# PSU.net
KiCad netlist of a schematic drawn in Altium Designer
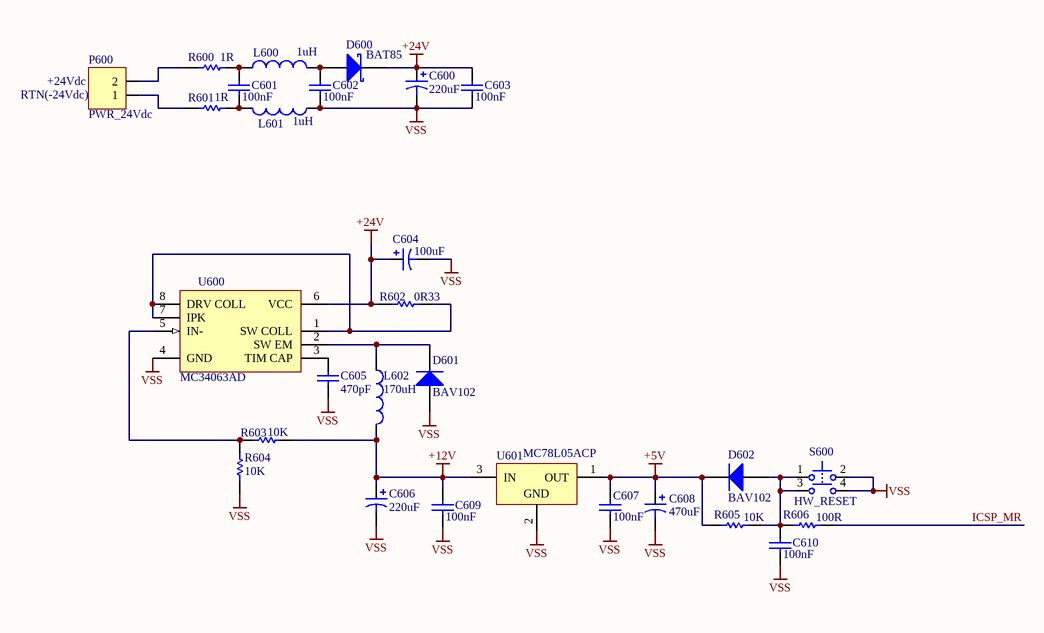
[diagram p0: PSU.SchDoc]

(export (version "E")
  (design (tool "Eeschema 10.0.6"))
  (components
    (comp (ref "C600")
      (value "220uF")
      (footprint "E")
      (description "Solid Aluminum Capacitor with Organic Semiconductor Electrolyte: 100uF, 10V, Bulk Pack")
      (fields (field (name "PUBLISHER") "Altium Limited"))
      (libsource (lib "Vishay Electrolytic Radial-Lead Capacitor") (part "94SA107X0010EBP"))
    )
    (comp (ref "C601")
      (value "100nF")
      (footprint "1206")
      (description "Ceramic Chip Capacitor - Standard")
      (fields (field (name "PUBLISHER") "Altium Limited"))
      (libsource (lib "KEMET Chip Capacitor") (part "C1206"))
    )
    (comp (ref "C602")
      (value "100nF")
      (footprint "1206")
      (description "Ceramic Chip Capacitor - Standard")
      (fields (field (name "PUBLISHER") "Altium Limited"))
      (libsource (lib "KEMET Chip Capacitor") (part "C1206"))
    )
    (comp (ref "C603")
      (value "100nF")
      (footprint "1206")
      (description "Ceramic Chip Capacitor - Standard")
      (fields (field (name "PUBLISHER") "Altium Limited"))
      (libsource (lib "KEMET Chip Capacitor") (part "C1206"))
    )
    (comp (ref "C604")
      (value "100uF")
      (footprint "CAPPR2-5X11")
      (description "Aluminum Electrolytic Capacitor, Radial Style with Long Leads: 10uF, 100V")
      (fields (field (name "PUBLISHER") "Altium Limited"))
      (libsource (lib "Vishay Roederstein Electrolytic Radial-Lead Capacitor") (part "EKA00AA210L00"))
    )
    (comp (ref "C605")
      (value "470pF")
      (footprint "0805")
      (description "Ceramic Chip Capacitor - Standard")
      (fields (field (name "PUBLISHER") "Altium Limited"))
      (libsource (lib "KEMET Chip Capacitor") (part "C0805"))
    )
    (comp (ref "C606")
      (value "220uF")
      (footprint "E")
      (description "Solid Aluminum Capacitor with Organic Semiconductor Electrolyte: 100uF, 10V, Bulk Pack")
      (fields (field (name "PUBLISHER") "Altium Limited"))
      (libsource (lib "Vishay Electrolytic Radial-Lead Capacitor") (part "94SA107X0010EBP"))
    )
    (comp (ref "C607")
      (value "100nF")
      (footprint "1206")
      (description "Ceramic Chip Capacitor - Standard")
      (fields (field (name "PUBLISHER") "Altium Limited"))
      (libsource (lib "KEMET Chip Capacitor") (part "C1206"))
    )
    (comp (ref "C608")
      (value "470uF")
      (footprint "CAPPR2-5X11")
      (description "Aluminum Electrolytic Capacitor, Radial Style with Long Leads: 10uF, 100V")
      (fields (field (name "PUBLISHER") "Altium Limited"))
      (libsource (lib "Vishay Roederstein Electrolytic Radial-Lead Capacitor") (part "EKA00AA210L00"))
    )
    (comp (ref "C609")
      (value "100nF")
      (footprint "1206")
      (description "Ceramic Chip Capacitor - Standard")
      (fields (field (name "PUBLISHER") "Altium Limited"))
      (libsource (lib "KEMET Chip Capacitor") (part "C1206"))
    )
    (comp (ref "C610")
      (value "100nF")
      (footprint "1206")
      (description "Ceramic Chip Capacitor - Standard")
      (fields (field (name "PUBLISHER") "Altium Limited"))
      (libsource (lib "KEMET Chip Capacitor") (part "C1206"))
    )
    (comp (ref "D600")
      (value "BAT85")
      (footprint "SOD68")
      (description "Schottky Barrier Diode")
      (fields (field (name "PUBLISHER") "Altium Limited"))
      (libsource (lib "Philips Discrete Diode - Schottky") (part "BAT85"))
    )
    (comp (ref "D601")
      (value "BAV102")
      (footprint "SOD80C")
      (description "General-purpose Diode")
      (fields (field (name "PUBLISHER") "Altium Limited"))
      (libsource (lib "Philips Discrete Diode - Switching") (part "BAV102"))
    )
    (comp (ref "D602")
      (value "BAV102")
      (footprint "SOD80C")
      (description "General-purpose Diode")
      (fields (field (name "PUBLISHER") "Altium Limited"))
      (libsource (lib "Philips Discrete Diode - Switching") (part "BAV102"))
    )
    (comp (ref "L600")
      (value "1uH")
      (footprint "PCMC063T")
      (description "SMT Power Choke Coil; Size 7.3×6.6×3.0mm, ±20% Tolerance, 1.0uH, 11A")
      (fields (field (name "PUBLISHER") "Altium Limited"))
      (libsource (lib "SSM Inductor") (part "PCMC063T-1R0MN"))
    )
    (comp (ref "L601")
      (value "1uH")
      (footprint "PCMC063T")
      (description "SMT Power Choke Coil; Size 7.3×6.6×3.0mm, ±20% Tolerance, 1.0uH, 11A")
      (fields (field (name "PUBLISHER") "Altium Limited"))
      (libsource (lib "SSM Inductor") (part "PCMC063T-1R0MN"))
    )
    (comp (ref "L602")
      (value "170uH")
      (footprint "Miscellaneous Devices:RB5-10.5")
      (description "SMT Power Choke Coil; Size 7.3×6.6×3.0mm, ±20% Tolerance, 0.82uH, 13A")
      (fields (field (name "PUBLISHER") "Altium Limited"))
      (libsource (lib "SSM Inductor") (part "PCMC063T-R82MN"))
    )
    (comp (ref "P600")
      (value "PWR_24Vdc")
      (footprint "TERMINAL BLOK 2")
      (description "Terminal blok 2")
      (libsource (lib "TERMINAL_CONNECOR_2") (part "Terminal blok 2 pina"))
    )
    (comp (ref "R600")
      (value "1R")
      (footprint "ERA-0805")
      (fields (field (name "PUBLISHER") "Altium Limited"))
      (libsource (lib "Panasonic Resistor") (part "ERAS"))
    )
    (comp (ref "R601")
      (value "1R")
      (footprint "ERA-0805")
      (fields (field (name "PUBLISHER") "Altium Limited"))
      (libsource (lib "Panasonic Resistor") (part "ERAS"))
    )
    (comp (ref "R602")
      (value "0R33")
      (footprint "ERA-0805")
      (fields (field (name "PUBLISHER") "Altium Limited"))
      (libsource (lib "Panasonic Resistor") (part "ERAS"))
    )
    (comp (ref "R603")
      (value "10K")
      (footprint "ERA-0805")
      (fields (field (name "PUBLISHER") "Altium Limited"))
      (libsource (lib "Panasonic Resistor") (part "ERAS"))
    )
    (comp (ref "R604")
      (value "10K")
      (footprint "ERA-0805")
      (fields (field (name "PUBLISHER") "Altium Limited"))
      (libsource (lib "Panasonic Resistor") (part "ERAS"))
    )
    (comp (ref "R605")
      (value "10K")
      (footprint "ERA-0805")
      (fields (field (name "PUBLISHER") "Altium Limited"))
      (libsource (lib "Panasonic Resistor") (part "ERAS"))
    )
    (comp (ref "R606")
      (value "100R")
      (footprint "ERA-0805")
      (fields (field (name "PUBLISHER") "Altium Limited"))
      (libsource (lib "Panasonic Resistor") (part "ERAS"))
    )
    (comp (ref "S600")
      (value "HW_RESET")
      (footprint "IT-2175")
      (description "Tactile Switch, DPST; Thru-Hole; Vertical; Rating DC 12V, 50mA (max)")
      (fields (field (name "PUBLISHER") "Altium Limited"))
      (libsource (lib "IL Switch Push Button") (part "IT-2175"))
    )
    (comp (ref "U600")
      (value "MC34063AD")
      (footprint "ON Semi Power Mgt Supervisory Cct:626-05")
      (description "DC-to-DC Converter Control Circuit")
      (fields (field (name "PUBLISHER") "Altium Limited"))
      (libsource (lib "ON Semi Power Mgt DC-DC Converter") (part "MC34063AD"))
    )
    (comp (ref "U601")
      (value "MC78L05ACP")
      (footprint "29-04")
      (description "3-Terminal Low-Current Positive Fixed Voltage Regulator")
      (fields (field (name "PUBLISHER") "Altium Limited"))
      (libsource (lib "Motorola Power Mgt Voltage Regulator") (part "MC78L05ACP"))
    )
  )
  (nets
    (net (code "1") (name "+5V") (class "Default")
      (node (ref "C607") (pin "2") (pinfunction "2_2") (pintype "passive"))
      (node (ref "C608") (pin "1") (pinfunction "1_1") (pintype "passive"))
      (node (ref "D602") (pin "2") (pinfunction "K_2") (pintype "passive"))
      (node (ref "R605") (pin "1") (pinfunction "1_1") (pintype "passive"))
      (node (ref "U601") (pin "1") (pinfunction "OUT_1") (pintype "power_in"))
    )
    (net (code "2") (name "+12V") (class "Default")
      (node (ref "C606") (pin "1") (pinfunction "1_1") (pintype "passive"))
      (node (ref "C609") (pin "2") (pinfunction "2_2") (pintype "passive"))
      (node (ref "L602") (pin "2") (pinfunction "2_2") (pintype "passive"))
      (node (ref "R603") (pin "2") (pinfunction "2_2") (pintype "passive"))
      (node (ref "U601") (pin "3") (pinfunction "IN_3") (pintype "power_in"))
    )
    (net (code "3") (name "+24V") (class "Default")
      (node (ref "C600") (pin "1") (pinfunction "1_1") (pintype "passive"))
      (node (ref "C603") (pin "2") (pinfunction "2_2") (pintype "passive"))
      (node (ref "C604") (pin "1") (pinfunction "1_1") (pintype "passive"))
      (node (ref "D600") (pin "2") (pinfunction "K_2") (pintype "passive"))
      (node (ref "R602") (pin "1") (pinfunction "1_1") (pintype "passive"))
      (node (ref "U600") (pin "6") (pinfunction "VCC_6") (pintype "power_in"))
    )
    (net (code "4") (name "/ICSP_MR") (class "Default")
      (node (ref "R606") (pin "2") (pinfunction "2_2") (pintype "passive"))
    )
    (net (code "5") (name "Net-(C601-Pad1)") (class "Default")
      (node (ref "C601") (pin "1") (pinfunction "1_1") (pintype "passive"))
      (node (ref "L601") (pin "2") (pinfunction "2_2") (pintype "passive"))
      (node (ref "R601") (pin "1") (pinfunction "1_1") (pintype "passive"))
    )
    (net (code "6") (name "Net-(C601-Pad2)") (class "Default")
      (node (ref "C601") (pin "2") (pinfunction "2_2") (pintype "passive"))
      (node (ref "L600") (pin "1") (pinfunction "1_1") (pintype "passive"))
      (node (ref "R600") (pin "1") (pinfunction "1_1") (pintype "passive"))
    )
    (net (code "7") (name "Net-(D600-A)") (class "Default")
      (node (ref "C602") (pin "2") (pinfunction "2_2") (pintype "passive"))
      (node (ref "D600") (pin "1") (pinfunction "A_1") (pintype "passive"))
      (node (ref "L600") (pin "2") (pinfunction "2_2") (pintype "passive"))
    )
    (net (code "8") (name "Net-(D601-K)") (class "Default")
      (node (ref "D601") (pin "2") (pinfunction "K_2") (pintype "passive"))
      (node (ref "L602") (pin "1") (pinfunction "1_1") (pintype "passive"))
      (node (ref "U600") (pin "2") (pinfunction "SW_EM_2") (pintype "passive"))
    )
    (net (code "9") (name "Net-(D602-A)") (class "Default")
      (node (ref "C610") (pin "2") (pinfunction "2_2") (pintype "passive"))
      (node (ref "D602") (pin "1") (pinfunction "A_1") (pintype "passive"))
      (node (ref "R605") (pin "2") (pinfunction "2_2") (pintype "passive"))
      (node (ref "R606") (pin "1") (pinfunction "1_1") (pintype "passive"))
      (node (ref "S600") (pin "1") (pinfunction "1_1") (pintype "passive"))
      (node (ref "S600") (pin "3") (pinfunction "3_3") (pintype "passive"))
    )
    (net (code "10") (name "Net-(P600-Pad1)") (class "Default")
      (node (ref "P600") (pin "1") (pinfunction "1_1") (pintype "passive"))
      (node (ref "R601") (pin "2") (pinfunction "2_2") (pintype "passive"))
    )
    (net (code "11") (name "Net-(P600-Pad2)") (class "Default")
      (node (ref "P600") (pin "2") (pinfunction "2_2") (pintype "passive"))
      (node (ref "R600") (pin "2") (pinfunction "2_2") (pintype "passive"))
    )
    (net (code "12") (name "Net-(U600-DRV_COLL)") (class "Default")
      (node (ref "R602") (pin "2") (pinfunction "2_2") (pintype "passive"))
      (node (ref "U600") (pin "1") (pinfunction "SW_COLL_1") (pintype "passive"))
      (node (ref "U600") (pin "7") (pinfunction "IPK_7") (pintype "passive"))
      (node (ref "U600") (pin "8") (pinfunction "DRV_COLL_8") (pintype "open_collector"))
    )
    (net (code "13") (name "Net-(U600-IN-)") (class "Default")
      (node (ref "R603") (pin "1") (pinfunction "1_1") (pintype "passive"))
      (node (ref "R604") (pin "2") (pinfunction "2_2") (pintype "passive"))
      (node (ref "U600") (pin "5") (pinfunction "IN-_5") (pintype "input"))
    )
    (net (code "14") (name "Net-(U600-TIM_CAP)") (class "Default")
      (node (ref "C605") (pin "2") (pinfunction "2_2") (pintype "passive"))
      (node (ref "U600") (pin "3") (pinfunction "TIM_CAP_3") (pintype "passive"))
    )
    (net (code "15") (name "VSS") (class "Default")
      (node (ref "C600") (pin "2") (pinfunction "2_2") (pintype "passive"))
      (node (ref "C602") (pin "1") (pinfunction "1_1") (pintype "passive"))
      (node (ref "C603") (pin "1") (pinfunction "1_1") (pintype "passive"))
      (node (ref "C604") (pin "2") (pinfunction "2_2") (pintype "passive"))
      (node (ref "C605") (pin "1") (pinfunction "1_1") (pintype "passive"))
      (node (ref "C606") (pin "2") (pinfunction "2_2") (pintype "passive"))
      (node (ref "C607") (pin "1") (pinfunction "1_1") (pintype "passive"))
      (node (ref "C608") (pin "2") (pinfunction "2_2") (pintype "passive"))
      (node (ref "C609") (pin "1") (pinfunction "1_1") (pintype "passive"))
      (node (ref "C610") (pin "1") (pinfunction "1_1") (pintype "passive"))
      (node (ref "D601") (pin "1") (pinfunction "A_1") (pintype "passive"))
      (node (ref "L601") (pin "1") (pinfunction "1_1") (pintype "passive"))
      (node (ref "R604") (pin "1") (pinfunction "1_1") (pintype "passive"))
      (node (ref "S600") (pin "2") (pinfunction "2_2") (pintype "passive"))
      (node (ref "S600") (pin "4") (pinfunction "4_4") (pintype "passive"))
      (node (ref "U600") (pin "4") (pinfunction "GND_4") (pintype "power_in"))
      (node (ref "U601") (pin "2") (pinfunction "GND_2") (pintype "power_in"))
    )
  )
)
